# HMC5883L_Breakout-v11.net
KiCad netlist of a schematic drawn in EAGLE
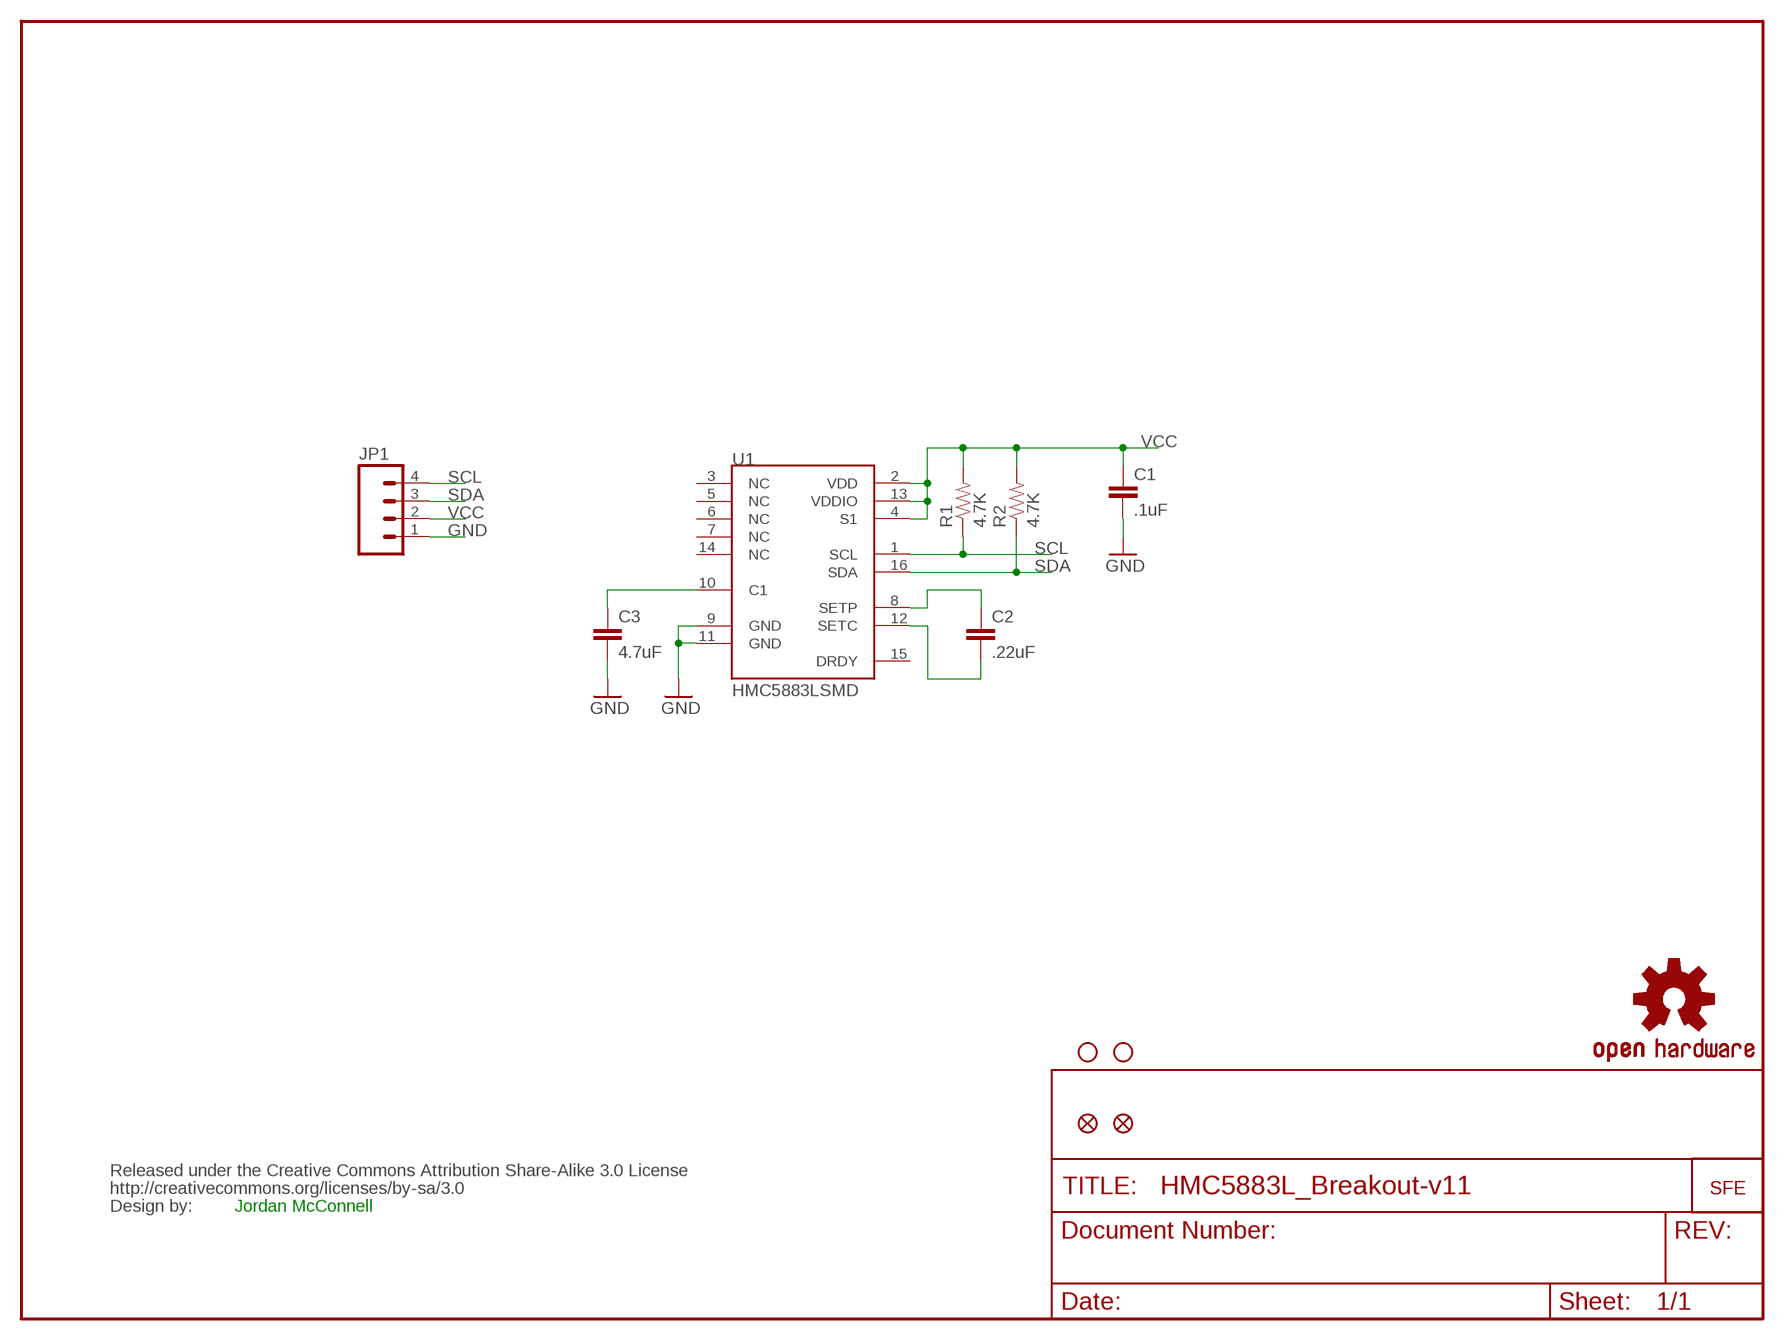
[diagram p0: schematic, sheet 1]

(export (version "E")
  (design (tool "Eeschema 10.0.6"))
  (components
    (comp (ref "C1")
      (value ".1uF")
      (footprint "eagle-import:0402-CAP")
      (libsource (lib "eagle-import") (part "CAP0402-CAP"))
    )
    (comp (ref "C2")
      (value ".22uF")
      (footprint "eagle-import:0402-CAP")
      (libsource (lib "eagle-import") (part "CAP0402-CAP"))
    )
    (comp (ref "C3")
      (value "4.7uF")
      (footprint "eagle-import:0402-CAP")
      (libsource (lib "eagle-import") (part "CAP0402-CAP"))
    )
    (comp (ref "JP1")
      (value "M04PTH")
      (footprint "eagle-import:1X04")
      (libsource (lib "eagle-import") (part "M04PTH"))
    )
    (comp (ref "JP2")
      (value "STAND-OFF")
      (footprint "eagle-import:STAND-OFF")
      (libsource (lib "eagle-import") (part "STAND-OFF"))
    )
    (comp (ref "JP3")
      (value "STAND-OFF")
      (footprint "eagle-import:STAND-OFF")
      (libsource (lib "eagle-import") (part "STAND-OFF"))
    )
    (comp (ref "JP4")
      (value "LOGO-SFESK")
      (footprint "eagle-import:SFE-LOGO-FLAME")
      (libsource (lib "eagle-import") (part "LOGO-SFESK"))
    )
    (comp (ref "JP5")
      (value "FIDUCIAL1X2.5")
      (footprint "eagle-import:FIDUCIAL-1X2.5")
      (libsource (lib "eagle-import") (part "FIDUCIAL1X2.5"))
    )
    (comp (ref "JP6")
      (value "FIDUCIAL1X2.5")
      (footprint "eagle-import:FIDUCIAL-1X2.5")
      (libsource (lib "eagle-import") (part "FIDUCIAL1X2.5"))
    )
    (comp (ref "R1")
      (value "4.7K")
      (footprint "eagle-import:0402-RES")
      (libsource (lib "eagle-import") (part "RESISTOR0402-RES"))
    )
    (comp (ref "R2")
      (value "4.7K")
      (footprint "eagle-import:0402-RES")
      (libsource (lib "eagle-import") (part "RESISTOR0402-RES"))
    )
    (comp (ref "U$1")
      (value "CREATIVE_COMMONS")
      (footprint "eagle-import:CREATIVE_COMMONS")
      (libsource (lib "eagle-import") (part "CREATIVE_COMMONS"))
    )
    (comp (ref "U$2")
      (value "OSHW-LOGOM")
      (footprint "eagle-import:OSHW-LOGO-M")
      (libsource (lib "eagle-import") (part "OSHW-LOGOM"))
    )
    (comp (ref "U1")
      (value "HMC5883LSMD")
      (footprint "eagle-import:16LPCC")
      (libsource (lib "eagle-import") (part "HMC5883LSMD"))
    )
  )
  (nets
    (net (code "1") (name "/SCL") (class "Default")
      (node (ref "JP1") (pin "4") (pinfunction "4_4") (pintype "passive"))
      (node (ref "R1") (pin "1") (pinfunction "1_1") (pintype "passive"))
      (node (ref "U1") (pin "1") (pinfunction "SCL_1") (pintype "bidirectional"))
    )
    (net (code "2") (name "/SDA") (class "Default")
      (node (ref "JP1") (pin "3") (pinfunction "3_3") (pintype "passive"))
      (node (ref "R2") (pin "1") (pinfunction "1_1") (pintype "passive"))
      (node (ref "U1") (pin "16") (pinfunction "SDA_16") (pintype "bidirectional"))
    )
    (net (code "3") (name "/VCC") (class "Default")
      (node (ref "C1") (pin "1") (pinfunction "1_1") (pintype "passive"))
      (node (ref "JP1") (pin "2") (pinfunction "2_2") (pintype "passive"))
      (node (ref "R1") (pin "2") (pinfunction "2_2") (pintype "passive"))
      (node (ref "R2") (pin "2") (pinfunction "2_2") (pintype "passive"))
      (node (ref "U1") (pin "13") (pinfunction "VDDIO_13") (pintype "bidirectional"))
      (node (ref "U1") (pin "2") (pinfunction "VDD_2") (pintype "bidirectional"))
      (node (ref "U1") (pin "4") (pinfunction "S1_4") (pintype "bidirectional"))
    )
    (net (code "4") (name "GND") (class "Default")
      (node (ref "C1") (pin "2") (pinfunction "2_2") (pintype "passive"))
      (node (ref "C3") (pin "2") (pinfunction "2_2") (pintype "passive"))
      (node (ref "JP1") (pin "1") (pinfunction "1_1") (pintype "passive"))
      (node (ref "U1") (pin "11") (pinfunction "GND_11") (pintype "bidirectional"))
      (node (ref "U1") (pin "9") (pinfunction "GND_9") (pintype "bidirectional"))
    )
    (net (code "5") (name "Net-(U1-C1)") (class "Default")
      (node (ref "C3") (pin "1") (pinfunction "1_1") (pintype "passive"))
      (node (ref "U1") (pin "10") (pinfunction "C1_10") (pintype "bidirectional"))
    )
    (net (code "6") (name "Net-(U1-SETC)") (class "Default")
      (node (ref "C2") (pin "2") (pinfunction "2_2") (pintype "passive"))
      (node (ref "U1") (pin "12") (pinfunction "SETC_12") (pintype "bidirectional"))
    )
    (net (code "7") (name "Net-(U1-SETP)") (class "Default")
      (node (ref "C2") (pin "1") (pinfunction "1_1") (pintype "passive"))
      (node (ref "U1") (pin "8") (pinfunction "SETP_8") (pintype "bidirectional"))
    )
    (net (code "8") (name "unconnected-(U1-DRDY-Pad15)") (class "Default")
      (node (ref "U1") (pin "15") (pinfunction "DRDY_15") (pintype "bidirectional"))
    )
    (net (code "9") (name "unconnected-(U1-NC-Pad3)") (class "Default")
      (node (ref "U1") (pin "3") (pinfunction "NC_3") (pintype "bidirectional"))
    )
    (net (code "10") (name "unconnected-(U1-NC-Pad5)") (class "Default")
      (node (ref "U1") (pin "5") (pinfunction "NC_5") (pintype "bidirectional"))
    )
    (net (code "11") (name "unconnected-(U1-NC-Pad6)") (class "Default")
      (node (ref "U1") (pin "6") (pinfunction "NC_6") (pintype "bidirectional"))
    )
    (net (code "12") (name "unconnected-(U1-NC-Pad7)") (class "Default")
      (node (ref "U1") (pin "7") (pinfunction "NC_7") (pintype "bidirectional"))
    )
    (net (code "13") (name "unconnected-(U1-NC-Pad14)") (class "Default")
      (node (ref "U1") (pin "14") (pinfunction "NC_14") (pintype "bidirectional"))
    )
  )
)
